# WirelessBuzzerv20.net
KiCad netlist of a schematic drawn in EAGLE
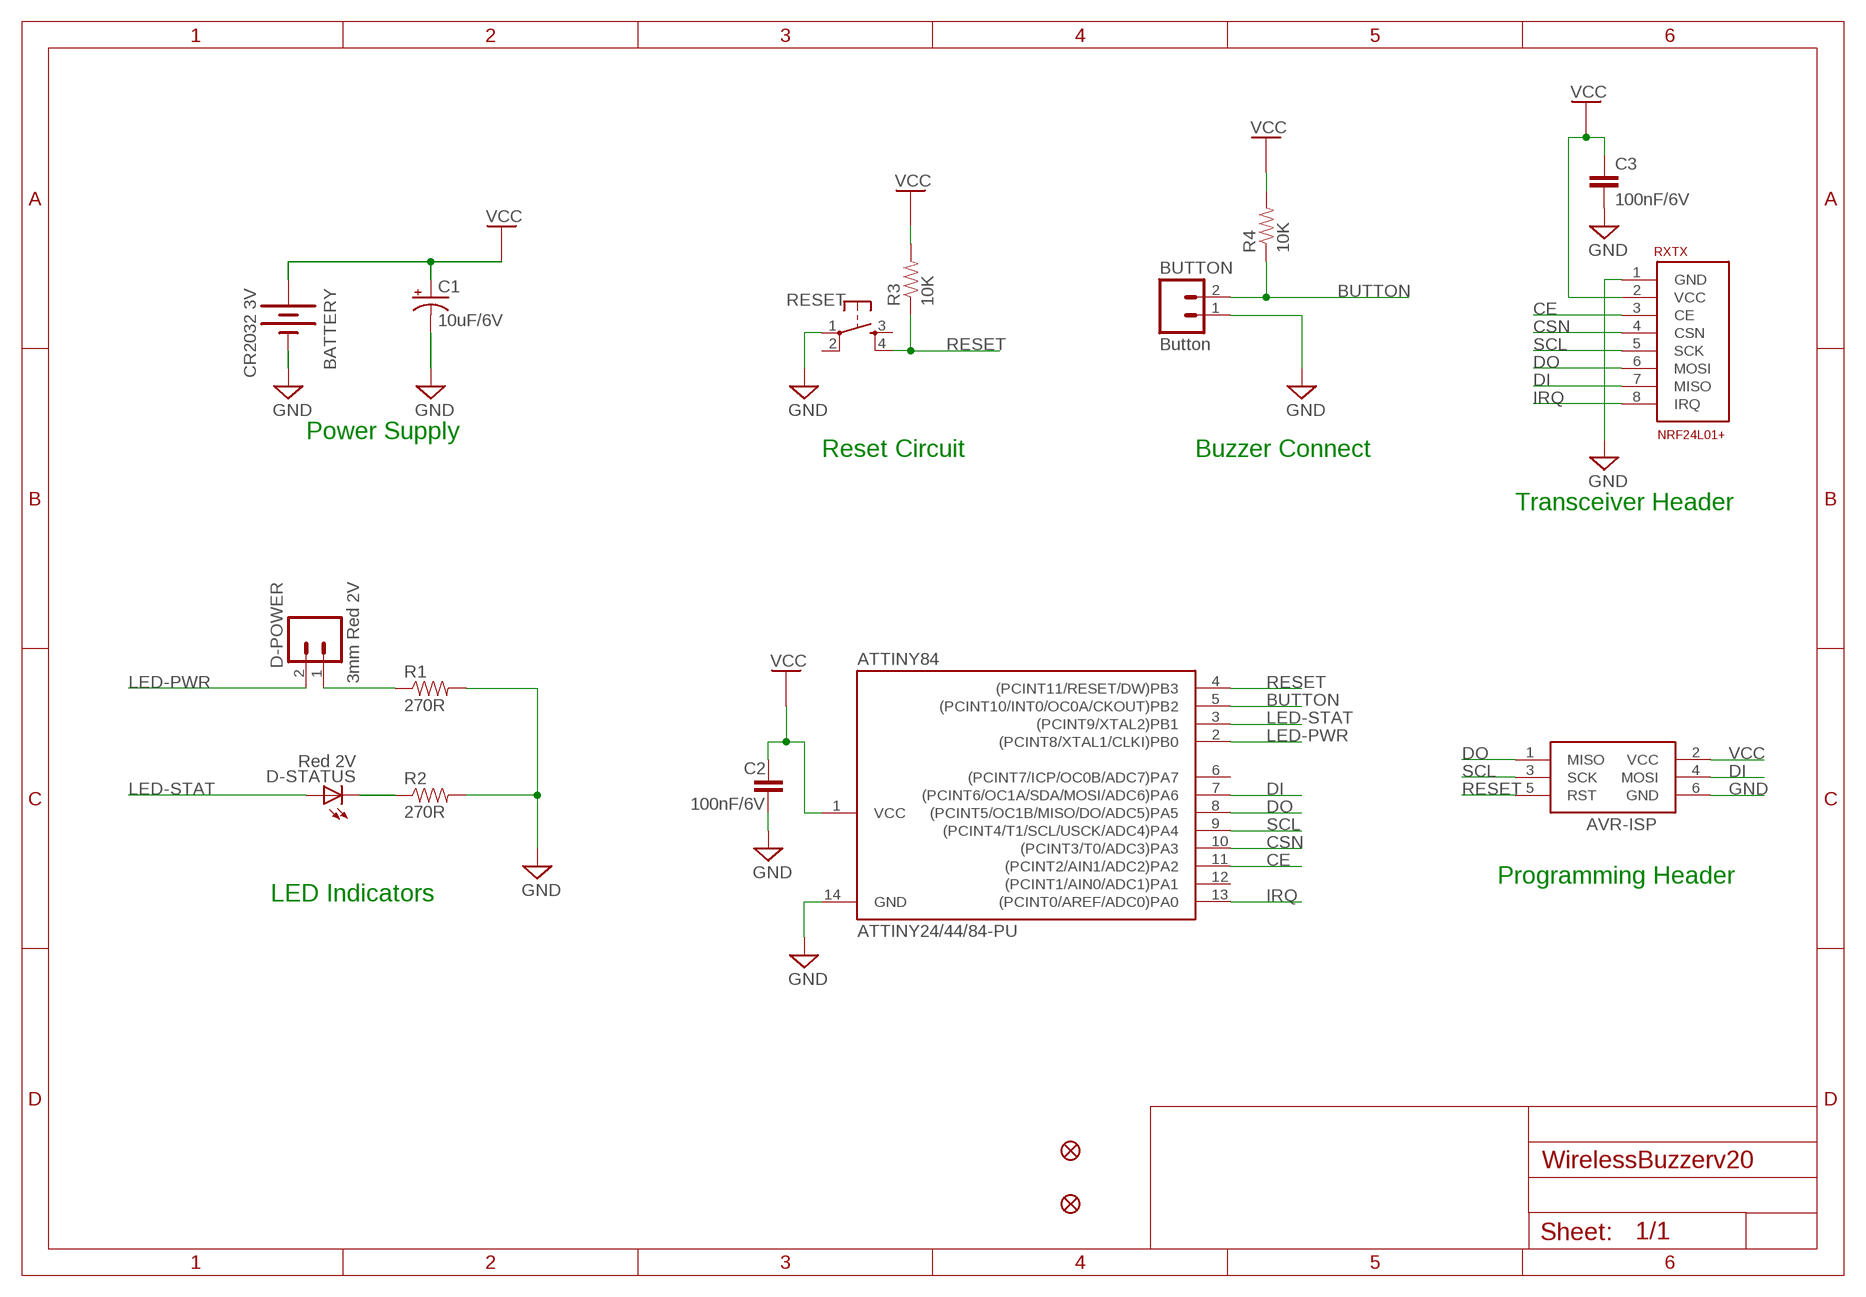
[diagram p0: schematic, sheet 1, part 1 of 2]
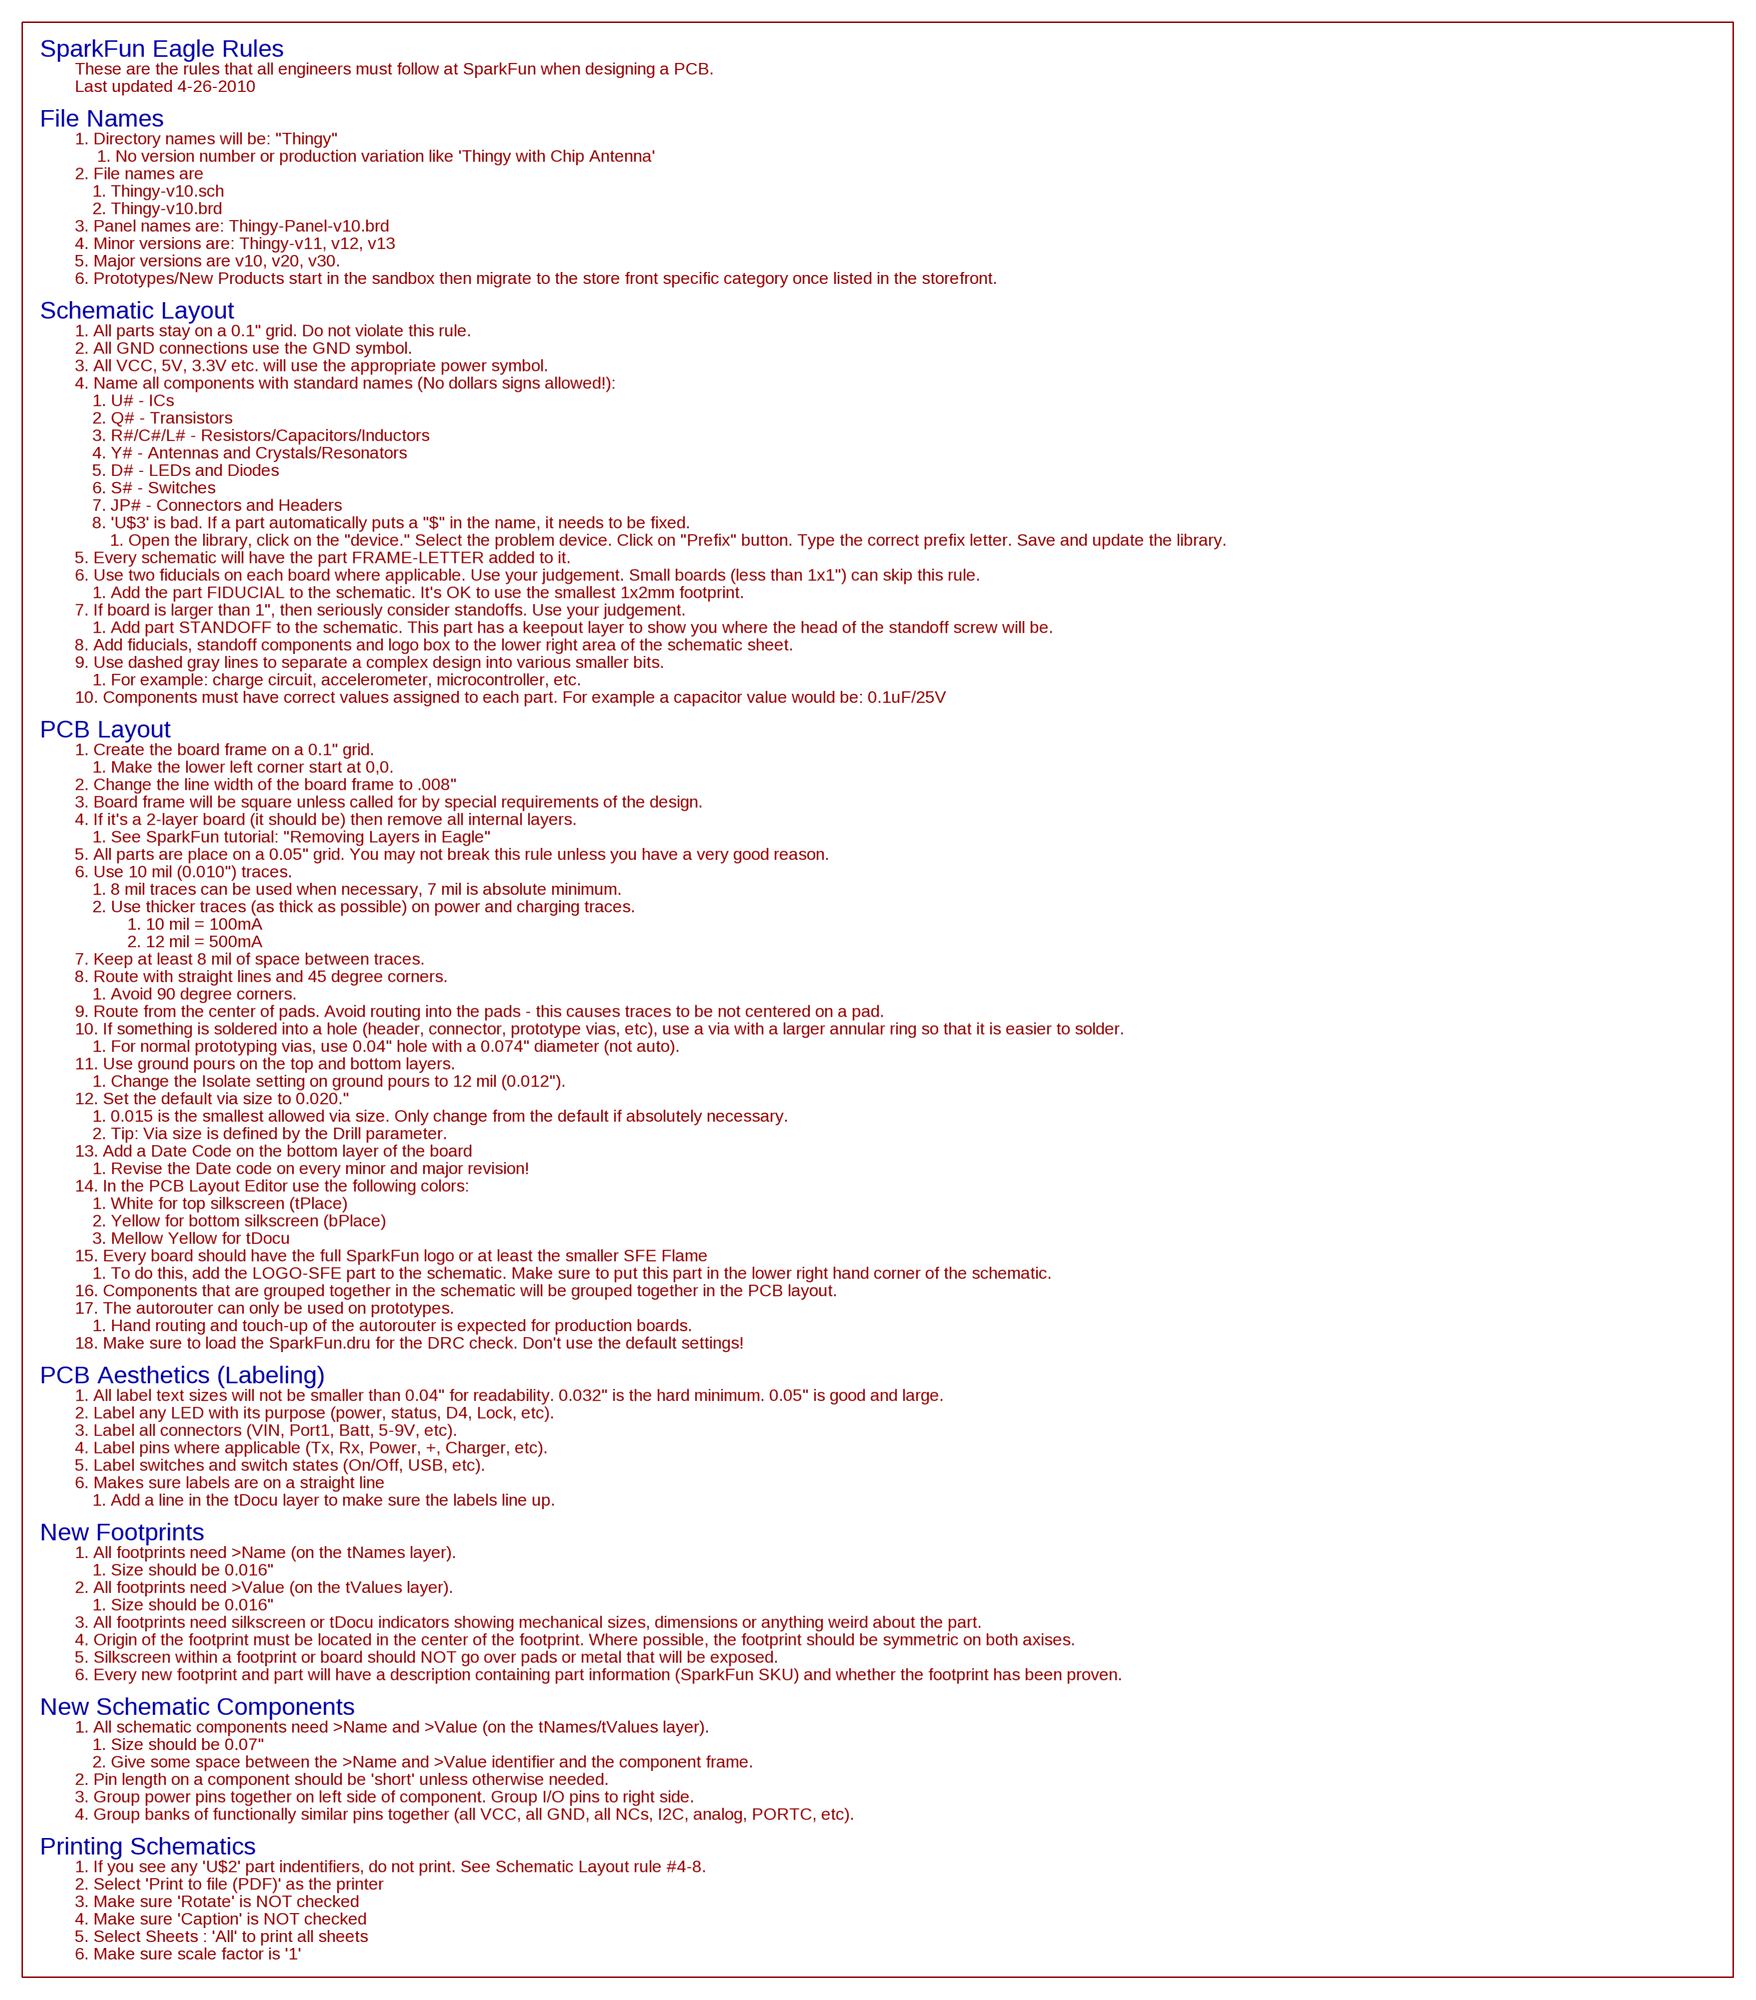
[diagram p1: schematic, sheet 1, part 2 of 2]

(export (version "E")
  (design (tool "Eeschema 10.0.6"))
  (components
    (comp (ref "ATTINY84")
      (value "ATTINY24/44/84-PU")
      (footprint "eagle-import:DIL14")
      (libsource (lib "eagle-import") (part "ATTINY24/44/84-PU"))
    )
    (comp (ref "AVR-ISP")
      (value "AVRISP-6")
      (footprint "eagle-import:AVRISP")
      (libsource (lib "eagle-import") (part "AVRISP-6"))
    )
    (comp (ref "BATTERY")
      (value "CR2032 3V")
      (footprint "eagle-import:BATTCOM_20MM_PTH")
      (libsource (lib "eagle-import") (part "BATTERY20PTH"))
    )
    (comp (ref "BUTTON")
      (value "Button")
      (footprint "eagle-import:1X02")
      (libsource (lib "eagle-import") (part "M02PTH"))
    )
    (comp (ref "C1")
      (value "10uF/6V")
      (footprint "eagle-import:EIA3528-KIT")
      (libsource (lib "eagle-import") (part "CAP_POL3528-KIT"))
    )
    (comp (ref "C2")
      (value "100nF/6V")
      (footprint "eagle-import:1206")
      (libsource (lib "eagle-import") (part "CAP1206"))
    )
    (comp (ref "C3")
      (value "100nF/6V")
      (footprint "eagle-import:1206")
      (libsource (lib "eagle-import") (part "CAP1206"))
    )
    (comp (ref "D-POWER")
      (value "3mm Red 2V")
      (footprint "eagle-import:1X02")
      (libsource (lib "eagle-import") (part "M02PTH"))
    )
    (comp (ref "D-STATUS")
      (value "Red 2V")
      (footprint "eagle-import:LED-1206")
      (libsource (lib "eagle-import") (part "LED1206"))
    )
    (comp (ref "FID1")
      (value "FIDUCIAL1.5X3")
      (footprint "eagle-import:FIDUCIAL-1.5X3")
      (libsource (lib "eagle-import") (part "FIDUCIAL1.5X3"))
    )
    (comp (ref "FID2")
      (value "FIDUCIAL1.5X3")
      (footprint "eagle-import:FIDUCIAL-1.5X3")
      (libsource (lib "eagle-import") (part "FIDUCIAL1.5X3"))
    )
    (comp (ref "R1")
      (value "270R")
      (footprint "eagle-import:1206")
      (libsource (lib "eagle-import") (part "RESISTOR1206"))
    )
    (comp (ref "R2")
      (value "270R")
      (footprint "eagle-import:1206")
      (libsource (lib "eagle-import") (part "RESISTOR1206"))
    )
    (comp (ref "R3")
      (value "10K")
      (footprint "eagle-import:1206")
      (libsource (lib "eagle-import") (part "RESISTOR1206"))
    )
    (comp (ref "R4")
      (value "10K")
      (footprint "eagle-import:1206")
      (libsource (lib "eagle-import") (part "RESISTOR1206"))
    )
    (comp (ref "RESET")
      (value "DTSM-6")
      (footprint "eagle-import:DTSM-6")
      (libsource (lib "eagle-import") (part "DTSM-6"))
    )
    (comp (ref "RXTX")
      (value "NRF24L01+")
      (footprint "eagle-import:NRF24L01+-HEADER")
      (libsource (lib "eagle-import") (part "NRF24L01+"))
    )
  )
  (nets
    (net (code "1") (name "/BUTTON") (class "Default")
      (node (ref "ATTINY84") (pin "5") (pinfunction "(PCINT10/INT0/OC0A/CKOUT)PB2_5") (pintype "bidirectional"))
      (node (ref "BUTTON") (pin "2") (pinfunction "2_2") (pintype "passive"))
      (node (ref "R4") (pin "1") (pinfunction "1_1") (pintype "passive"))
    )
    (net (code "2") (name "/CE") (class "Default")
      (node (ref "ATTINY84") (pin "11") (pinfunction "(PCINT2/AIN1/ADC2)PA2_11") (pintype "bidirectional"))
      (node (ref "RXTX") (pin "3") (pinfunction "CE_3") (pintype "bidirectional"))
    )
    (net (code "3") (name "/CSN") (class "Default")
      (node (ref "ATTINY84") (pin "10") (pinfunction "(PCINT3/T0/ADC3)PA3_10") (pintype "bidirectional"))
      (node (ref "RXTX") (pin "4") (pinfunction "CSN_4") (pintype "bidirectional"))
    )
    (net (code "4") (name "/DI") (class "Default")
      (node (ref "ATTINY84") (pin "7") (pinfunction "(PCINT6/OC1A/SDA/MOSI/ADC6)PA6_7") (pintype "bidirectional"))
      (node (ref "AVR-ISP") (pin "4") (pinfunction "MOSI_4") (pintype "output"))
      (node (ref "RXTX") (pin "7") (pinfunction "MISO_7") (pintype "bidirectional"))
    )
    (net (code "5") (name "/DO") (class "Default")
      (node (ref "ATTINY84") (pin "8") (pinfunction "(PCINT5/OC1B/MISO/DO/ADC5)PA5_8") (pintype "bidirectional"))
      (node (ref "AVR-ISP") (pin "1") (pinfunction "MISO_1") (pintype "input"))
      (node (ref "RXTX") (pin "6") (pinfunction "MOSI_6") (pintype "bidirectional"))
    )
    (net (code "6") (name "/IRQ") (class "Default")
      (node (ref "ATTINY84") (pin "13") (pinfunction "(PCINT0/AREF/ADC0)PA0_13") (pintype "bidirectional"))
      (node (ref "RXTX") (pin "8") (pinfunction "IRQ_8") (pintype "bidirectional"))
    )
    (net (code "7") (name "/LED-PWR") (class "Default")
      (node (ref "ATTINY84") (pin "2") (pinfunction "(PCINT8/XTAL1/CLKI)PB0_2") (pintype "bidirectional"))
      (node (ref "D-POWER") (pin "2") (pinfunction "2_2") (pintype "passive"))
    )
    (net (code "8") (name "/LED-STAT") (class "Default")
      (node (ref "ATTINY84") (pin "3") (pinfunction "(PCINT9/XTAL2)PB1_3") (pintype "bidirectional"))
      (node (ref "D-STATUS") (pin "A") (pinfunction "A_A") (pintype "passive"))
    )
    (net (code "9") (name "/RESET") (class "Default")
      (node (ref "ATTINY84") (pin "4") (pinfunction "(PCINT11/RESET/DW)PB3_4") (pintype "bidirectional"))
      (node (ref "AVR-ISP") (pin "5") (pinfunction "RST_5") (pintype "output"))
      (node (ref "R3") (pin "1") (pinfunction "1_1") (pintype "passive"))
      (node (ref "RESET") (pin "4") (pinfunction "4_4") (pintype "passive"))
    )
    (net (code "10") (name "/SCL") (class "Default")
      (node (ref "ATTINY84") (pin "9") (pinfunction "(PCINT4/T1/SCL/USCK/ADC4)PA4_9") (pintype "bidirectional"))
      (node (ref "AVR-ISP") (pin "3") (pinfunction "SCK_3") (pintype "output"))
      (node (ref "RXTX") (pin "5") (pinfunction "SCK_5") (pintype "bidirectional"))
    )
    (net (code "11") (name "GND") (class "Default")
      (node (ref "ATTINY84") (pin "14") (pinfunction "GND_14") (pintype "power_in"))
      (node (ref "AVR-ISP") (pin "6") (pinfunction "GND_6") (pintype "power_in"))
      (node (ref "BATTERY") (pin "2") (pinfunction "-_2") (pintype "power_in"))
      (node (ref "BUTTON") (pin "1") (pinfunction "1_1") (pintype "passive"))
      (node (ref "C1") (pin "C") (pinfunction "-_C") (pintype "passive"))
      (node (ref "C2") (pin "2") (pinfunction "2_2") (pintype "passive"))
      (node (ref "C3") (pin "2") (pinfunction "2_2") (pintype "passive"))
      (node (ref "R1") (pin "2") (pinfunction "2_2") (pintype "passive"))
      (node (ref "R2") (pin "2") (pinfunction "2_2") (pintype "passive"))
      (node (ref "RESET") (pin "1") (pinfunction "1_1") (pintype "passive"))
      (node (ref "RXTX") (pin "1") (pinfunction "GND_1") (pintype "power_in"))
    )
    (net (code "12") (name "Net-(D-POWER-Pad1)") (class "Default")
      (node (ref "D-POWER") (pin "1") (pinfunction "1_1") (pintype "passive"))
      (node (ref "R1") (pin "1") (pinfunction "1_1") (pintype "passive"))
    )
    (net (code "13") (name "Net-(D-STATUS-PadC)") (class "Default")
      (node (ref "D-STATUS") (pin "C") (pinfunction "C_C") (pintype "passive"))
      (node (ref "R2") (pin "1") (pinfunction "1_1") (pintype "passive"))
    )
    (net (code "14") (name "VCC") (class "Default")
      (node (ref "ATTINY84") (pin "1") (pinfunction "VCC_1") (pintype "power_in"))
      (node (ref "AVR-ISP") (pin "2") (pinfunction "VCC_2") (pintype "power_in"))
      (node (ref "BATTERY") (pin "1") (pinfunction "+_1") (pintype "power_in"))
      (node (ref "C1") (pin "A") (pinfunction "+_A") (pintype "passive"))
      (node (ref "C2") (pin "1") (pinfunction "1_1") (pintype "passive"))
      (node (ref "C3") (pin "1") (pinfunction "1_1") (pintype "passive"))
      (node (ref "R3") (pin "2") (pinfunction "2_2") (pintype "passive"))
      (node (ref "R4") (pin "2") (pinfunction "2_2") (pintype "passive"))
      (node (ref "RXTX") (pin "2") (pinfunction "VCC_2") (pintype "power_in"))
    )
    (net (code "15") (name "unconnected-(ATTINY84-(PCINT1{slash}AIN0{slash}ADC1)PA1-Pad12)") (class "Default")
      (node (ref "ATTINY84") (pin "12") (pinfunction "(PCINT1/AIN0/ADC1)PA1_12") (pintype "bidirectional"))
    )
    (net (code "16") (name "unconnected-(ATTINY84-(PCINT7{slash}ICP{slash}OC0B{slash}ADC7)PA7-Pad6)") (class "Default")
      (node (ref "ATTINY84") (pin "6") (pinfunction "(PCINT7/ICP/OC0B/ADC7)PA7_6") (pintype "bidirectional"))
    )
    (net (code "17") (name "unconnected-(RESET-Pad2)") (class "Default")
      (node (ref "RESET") (pin "2") (pinfunction "2_2") (pintype "passive"))
    )
    (net (code "18") (name "unconnected-(RESET-Pad3)") (class "Default")
      (node (ref "RESET") (pin "3") (pinfunction "3_3") (pintype "passive"))
    )
  )
)
